# main.net
KiCad netlist of a schematic drawn in Altium Designer
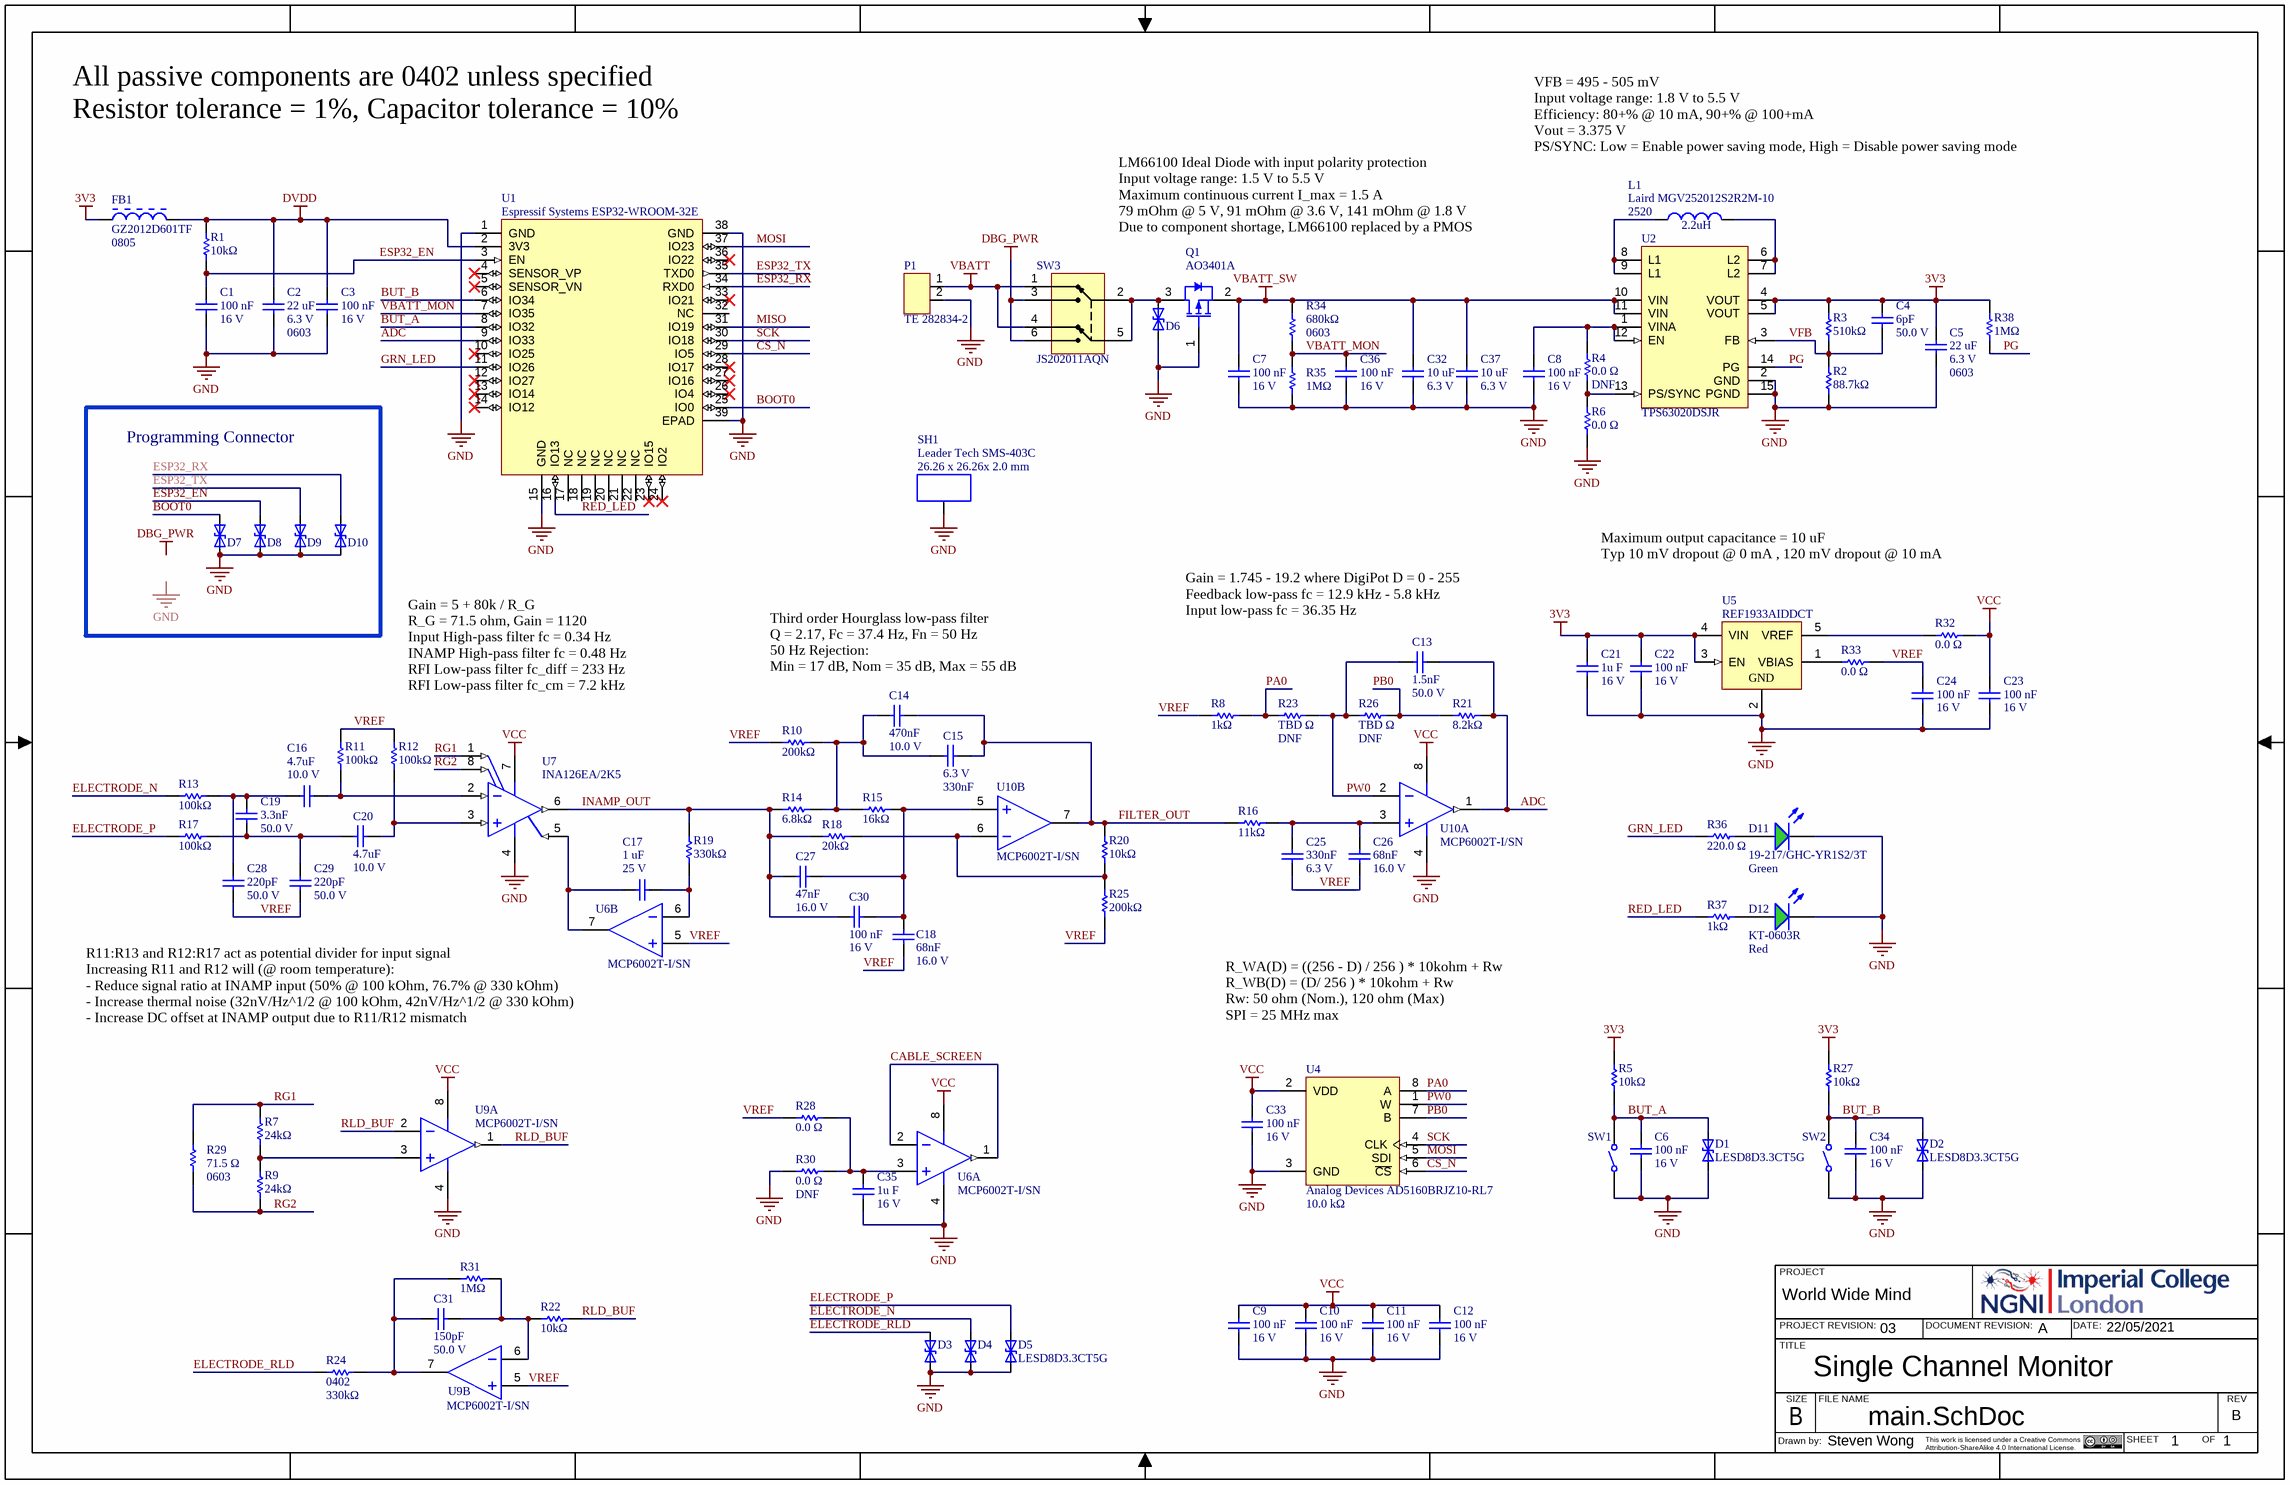
[diagram p0: main.SchDoc]

(export (version "E")
  (design (tool "Eeschema 10.0.6"))
  (components
    (comp (ref "C1")
      (value "100nF")
      (footprint "CAPC1005X56X25NL10T15")
      (description "Ceramic capacitor SMD-0402 100nF /16V X7R# K +-10%, Samsung, RoHS")
      (fields
        (field (name "CAPACITANCE") "100 nF")
        (field (name "VOLTAGE RATING") "16 V")
        (field (name "LCSC PART #") "C1525")
      )
      (libsource (lib "CommunityVault") (part "CMP-bf2276a55d9a60e5-19"))
    )
    (comp (ref "C2")
      (value "Murata GRM188R60G226MEA0L")
      (footprint "CAPC1608X90X35NL10T15")
      (description "Cap Ceramic 22uF 6.3V X5R 20% SMD 0603 85C Embossed T/R")
      (fields
        (field (name "CAPACITANCE") "22 uF")
        (field (name "VOLTAGE RATING (DC)") "6.3 V")
        (field (name "MANUFACTURER PART NUMBER") "GRM188R60G226MEA0L")
        (field (name "PACKAGE") "0603")
        (field (name "LCSC PART #") "C59461")
      )
      (libsource (lib "CommunityVault") (part "CMP-122043-3"))
    )
    (comp (ref "C3")
      (value "100nF")
      (footprint "CAPC1005X56X25NL10T15")
      (description "Ceramic capacitor SMD-0402 100nF /16V X7R# K +-10%, Samsung, RoHS")
      (fields
        (field (name "CAPACITANCE") "100 nF")
        (field (name "VOLTAGE RATING") "16 V")
        (field (name "LCSC PART #") "C1525")
      )
      (libsource (lib "CommunityVault") (part "CMP-bf2276a55d9a60e5-19"))
    )
    (comp (ref "C4")
      (value "AVX Interconnect / Elco 04025A6R0DAT2A")
      (footprint "CAPC1005X60X25NL10T15")
      (description "Multilayer Ceramic Capacitors MLCC - SMD/SMT 50volts 6pF C0G")
      (fields
        (field (name "CAPACITANCE") "6pF")
        (field (name "VOLTAGE RATING (DC)") "50.0 V")
        (field (name "MANUFACTURER PART NUMBER") "04025A6R0DAT2A")
        (field (name "LCSC PART #") "C30274")
      )
      (libsource (lib "CommunityVault") (part "CMP-173346-2"))
    )
    (comp (ref "C5")
      (value "Murata GRM188R60G226MEA0L")
      (footprint "CAPC1608X90X35NL10T15")
      (description "Cap Ceramic 22uF 6.3V X5R 20% SMD 0603 85C Embossed T/R")
      (fields
        (field (name "CAPACITANCE") "22 uF")
        (field (name "VOLTAGE RATING (DC)") "6.3 V")
        (field (name "MANUFACTURER PART NUMBER") "GRM188R60G226MEA0L")
        (field (name "PACKAGE") "0603")
        (field (name "LCSC PART #") "C59461")
      )
      (libsource (lib "CommunityVault") (part "CMP-122043-3"))
    )
    (comp (ref "C6")
      (value "100nF")
      (footprint "CAPC1005X56X25NL10T15")
      (description "Ceramic capacitor SMD-0402 100nF /16V X7R# K +-10%, Samsung, RoHS")
      (fields
        (field (name "CAPACITANCE") "100 nF")
        (field (name "VOLTAGE RATING") "16 V")
        (field (name "LCSC PART #") "C1525")
      )
      (libsource (lib "CommunityVault") (part "CMP-bf2276a55d9a60e5-19"))
    )
    (comp (ref "C7")
      (value "100nF")
      (footprint "CAPC1005X56X25NL10T15")
      (description "Ceramic capacitor SMD-0402 100nF /16V X7R# K +-10%, Samsung, RoHS")
      (fields
        (field (name "CAPACITANCE") "100 nF")
        (field (name "VOLTAGE RATING") "16 V")
        (field (name "LCSC PART #") "C1525")
      )
      (libsource (lib "CommunityVault") (part "CMP-bf2276a55d9a60e5-19"))
    )
    (comp (ref "C8")
      (value "100nF")
      (footprint "CAPC1005X56X25NL10T15")
      (description "Ceramic capacitor SMD-0402 100nF /16V X7R# K +-10%, Samsung, RoHS")
      (fields
        (field (name "CAPACITANCE") "100 nF")
        (field (name "VOLTAGE RATING") "16 V")
        (field (name "LCSC PART #") "C1525")
      )
      (libsource (lib "CommunityVault") (part "CMP-bf2276a55d9a60e5-19"))
    )
    (comp (ref "C9")
      (value "100nF")
      (footprint "CAPC1005X56X25NL10T15")
      (description "Ceramic capacitor SMD-0402 100nF /16V X7R# K +-10%, Samsung, RoHS")
      (fields
        (field (name "CAPACITANCE") "100 nF")
        (field (name "VOLTAGE RATING") "16 V")
        (field (name "LCSC PART #") "C1525")
      )
      (libsource (lib "CommunityVault") (part "CMP-bf2276a55d9a60e5-19"))
    )
    (comp (ref "C10")
      (value "100nF")
      (footprint "CAPC1005X56X25NL10T15")
      (description "Ceramic capacitor SMD-0402 100nF /16V X7R# K +-10%, Samsung, RoHS")
      (fields
        (field (name "CAPACITANCE") "100 nF")
        (field (name "VOLTAGE RATING") "16 V")
        (field (name "LCSC PART #") "C1525")
      )
      (libsource (lib "CommunityVault") (part "CMP-bf2276a55d9a60e5-19"))
    )
    (comp (ref "C11")
      (value "100nF")
      (footprint "CAPC1005X56X25NL10T15")
      (description "Ceramic capacitor SMD-0402 100nF /16V X7R# K +-10%, Samsung, RoHS")
      (fields
        (field (name "CAPACITANCE") "100 nF")
        (field (name "VOLTAGE RATING") "16 V")
        (field (name "LCSC PART #") "C1525")
      )
      (libsource (lib "CommunityVault") (part "CMP-bf2276a55d9a60e5-19"))
    )
    (comp (ref "C12")
      (value "100nF")
      (footprint "CAPC1005X56X25NL10T15")
      (description "Ceramic capacitor SMD-0402 100nF /16V X7R# K +-10%, Samsung, RoHS")
      (fields
        (field (name "CAPACITANCE") "100 nF")
        (field (name "VOLTAGE RATING") "16 V")
        (field (name "LCSC PART #") "C1525")
      )
      (libsource (lib "CommunityVault") (part "CMP-bf2276a55d9a60e5-19"))
    )
    (comp (ref "C13")
      (value "AVX Interconnect / Elco 04025C152KAT2A")
      (footprint "CAPC1005X56X25NL10T15")
      (description "Cap Ceramic 0.0015uF 50V X7R 10% SMD 0402 125C Paper T/R")
      (fields
        (field (name "MANUFACTURER PART NUMBER") "04025C152KAT2A")
        (field (name "CAPACITANCE") "1.5nF")
        (field (name "VOLTAGE RATING (DC)") "50.0 V")
        (field (name "LCSC PART #") "C23967")
      )
      (libsource (lib "CommunityVault") (part "CMP-126494-2"))
    )
    (comp (ref "C14")
      (value "AVX Interconnect / Elco 0402ZD474KAT2A")
      (footprint "CAPC1005X56X25NL10T15")
      (description "Multilayer Ceramic Capacitors MLCC - SMD/SMT 10volts 0.47uF 10% X5R")
      (fields
        (field (name "MANUFACTURER PART NUMBER") "0402ZD474KAT2A")
        (field (name "CAPACITANCE") "470nF")
        (field (name "VOLTAGE RATING (DC)") "10.0 V")
        (field (name "LCSC PART #") "C47339")
      )
      (libsource (lib "CommunityVault") (part "CMP-4106702-2"))
    )
    (comp (ref "C15")
      (value "CL05A334KQ5NNNC")
      (footprint "CAPC1005X55X25NL05T10")
      (description "CAP CER 0.33UF 10V 10% X5R 0402")
      (fields
        (field (name "VOLTAGE RATING (DC)") "6.3 V")
        (field (name "CAPACITANCE") "330nF")
        (field (name "LCSC PART #") "C307420")
      )
      (libsource (lib "CommunityVault") (part "CMP-119553-3"))
    )
    (comp (ref "C16")
      (value "CL05A475MP5NRNC")
      (footprint "CAPC1005X56X25NL10T15")
      (description "T&R / COMMERCIAL CHIP")
      (fields
        (field (name "CAPACITANCE") "4.7uF")
        (field (name "VOLTAGE RATING (DC)") "10.0 V")
        (field (name "LCSC PART #") "C23733")
      )
      (libsource (lib "CommunityVault") (part "CMP-19563753-2"))
    )
    (comp (ref "C17")
      (value "Samsung CL05A105KA5NQNC")
      (footprint "PCB-515da9ytrm2wahx6tw11-1")
      (description "Cap Ceramic 1uF 25V X5R 10% SMD 0402 85°C Cardboard T/R")
      (fields
        (field (name "VOLTAGE RATING (DC)") "25 V")
        (field (name "CAPACITANCE") "1 uF")
        (field (name "MANUFACTURER PART NUMBER") "CL05A105KA5NQNC")
        (field (name "LCSC PART #") "C52923")
      )
      (libsource (lib "CommunityVault") (part "CMP-8f214705328650e6-4"))
    )
    (comp (ref "C18")
      (value "Kemet C0402C683K4RACTU")
      (footprint "CAPC1005X55X30NL05T10")
      (description "CAP CER 0.068UF 16V 10% X7R 0402")
      (fields
        (field (name "CAPACITANCE") "68nF")
        (field (name "VOLTAGE RATING (DC)") "16.0 V")
        (field (name "MANUFACTURER PART NUMBER") "C0402C683K4RACTU")
        (field (name "LCSC PART #") "C12529")
      )
      (libsource (lib "CommunityVault") (part "CMP-124577-2"))
    )
    (comp (ref "C19")
      (value "AVX Interconnect / Elco 04025C332KAT2A")
      (footprint "CAPC1005X56X25NL10T15")
      (description "AVX   04025C332KAT2A   CAP, MLCC, X7R, 3.3NF, 50V, 0402")
      (fields
        (field (name "CAPACITANCE") "3.3nF")
        (field (name "VOLTAGE RATING (DC)") "50.0 V")
        (field (name "MANUFACTURER PART NUMBER") "04025C332KAT2A")
        (field (name "LCSC PART #") "C26404")
      )
      (libsource (lib "CommunityVault") (part "CMP-128367-2"))
    )
    (comp (ref "C20")
      (value "CL05A475MP5NRNC")
      (footprint "CAPC1005X56X25NL10T15")
      (description "T&R / COMMERCIAL CHIP")
      (fields
        (field (name "CAPACITANCE") "4.7uF")
        (field (name "VOLTAGE RATING (DC)") "10.0 V")
        (field (name "LCSC PART #") "C23733")
      )
      (libsource (lib "CommunityVault") (part "CMP-19563753-2"))
    )
    (comp (ref "C21")
      (value "Murata GRM155R61C105KA12D")
      (footprint "CAPC1005X55X25NL05T10")
      (description "Cap Ceramic 1uF 16V X5R 10% SMD 0402 85C Paper T/R")
      (fields
        (field (name "CAPACITANCE") "1u F")
        (field (name "VOLTAGE RATING (DC)") "16 V")
        (field (name "MANUFACTURER PART NUMBER") "GRM155R61C105KA12D")
        (field (name "LCSC PART #") "C52923")
      )
      (libsource (lib "CommunityVault") (part "CMP-7562325-2"))
    )
    (comp (ref "C22")
      (value "100nF")
      (footprint "CAPC1005X56X25NL10T15")
      (description "Ceramic capacitor SMD-0402 100nF /16V X7R# K +-10%, Samsung, RoHS")
      (fields
        (field (name "CAPACITANCE") "100 nF")
        (field (name "VOLTAGE RATING") "16 V")
        (field (name "LCSC PART #") "C1525")
      )
      (libsource (lib "CommunityVault") (part "CMP-bf2276a55d9a60e5-19"))
    )
    (comp (ref "C23")
      (value "100nF")
      (footprint "CAPC1005X56X25NL10T15")
      (description "Ceramic capacitor SMD-0402 100nF /16V X7R# K +-10%, Samsung, RoHS")
      (fields
        (field (name "CAPACITANCE") "100 nF")
        (field (name "VOLTAGE RATING") "16 V")
        (field (name "LCSC PART #") "C1525")
      )
      (libsource (lib "CommunityVault") (part "CMP-bf2276a55d9a60e5-19"))
    )
    (comp (ref "C24")
      (value "100nF")
      (footprint "CAPC1005X56X25NL10T15")
      (description "Ceramic capacitor SMD-0402 100nF /16V X7R# K +-10%, Samsung, RoHS")
      (fields
        (field (name "CAPACITANCE") "100 nF")
        (field (name "VOLTAGE RATING") "16 V")
        (field (name "LCSC PART #") "C1525")
      )
      (libsource (lib "CommunityVault") (part "CMP-bf2276a55d9a60e5-19"))
    )
    (comp (ref "C25")
      (value "CL05A334KQ5NNNC")
      (footprint "CAPC1005X55X25NL05T10")
      (description "CAP CER 0.33UF 10V 10% X5R 0402")
      (fields
        (field (name "VOLTAGE RATING (DC)") "6.3 V")
        (field (name "CAPACITANCE") "330nF")
        (field (name "LCSC PART #") "C307420")
      )
      (libsource (lib "CommunityVault") (part "CMP-119553-3"))
    )
    (comp (ref "C26")
      (value "Kemet C0402C683K4RACTU")
      (footprint "CAPC1005X55X30NL05T10")
      (description "CAP CER 0.068UF 16V 10% X7R 0402")
      (fields
        (field (name "CAPACITANCE") "68nF")
        (field (name "VOLTAGE RATING (DC)") "16.0 V")
        (field (name "MANUFACTURER PART NUMBER") "C0402C683K4RACTU")
        (field (name "LCSC PART #") "C12529")
      )
      (libsource (lib "CommunityVault") (part "CMP-124577-2"))
    )
    (comp (ref "C27")
      (value "AVX Interconnect / Elco 04023C473KAT2A")
      (footprint "CAPC1005X56X25NL10T15")
      (description "Multilayer Ceramic Capacitors MLCC - SMD/SMT 25volts 0.047uF 10% X7R 0402 SIZE")
      (fields
        (field (name "CAPACITANCE") "47nF")
        (field (name "VOLTAGE RATING (DC)") "16.0 V")
        (field (name "MANUFACTURER PART NUMBER") "04023C473KAT2A")
        (field (name "LCSC PART #") "C26403")
      )
      (libsource (lib "CommunityVault") (part "CMP-8988077-2"))
    )
    (comp (ref "C28")
      (value "Kemet C0402C221K5RACAUTO")
      (footprint "CAPC1005X55X30NL05T10")
      (description "CAPACITOR, 0402, X7R, 50V, 220PF")
      (fields
        (field (name "MANUFACTURER PART NUMBER") "C0402C221K5RACAUTO")
        (field (name "CAPACITANCE") "220pF")
        (field (name "VOLTAGE RATING (DC)") "50.0 V")
        (field (name "LCSC PART #") "C1530")
      )
      (libsource (lib "CommunityVault") (part "CMP-3913259-2"))
    )
    (comp (ref "C29")
      (value "Kemet C0402C221K5RACAUTO")
      (footprint "CAPC1005X55X30NL05T10")
      (description "CAPACITOR, 0402, X7R, 50V, 220PF")
      (fields
        (field (name "MANUFACTURER PART NUMBER") "C0402C221K5RACAUTO")
        (field (name "CAPACITANCE") "220pF")
        (field (name "VOLTAGE RATING (DC)") "50.0 V")
        (field (name "LCSC PART #") "C1530")
      )
      (libsource (lib "CommunityVault") (part "CMP-3913259-2"))
    )
    (comp (ref "C30")
      (value "100nF")
      (footprint "CAPC1005X56X25NL10T15")
      (description "Ceramic capacitor SMD-0402 100nF /16V X7R# K +-10%, Samsung, RoHS")
      (fields
        (field (name "CAPACITANCE") "100 nF")
        (field (name "VOLTAGE RATING") "16 V")
        (field (name "LCSC PART #") "C1525")
      )
      (libsource (lib "CommunityVault") (part "CMP-bf2276a55d9a60e5-19"))
    )
    (comp (ref "C31")
      (value "AVX Interconnect / Elco 04025A151JAT2A")
      (footprint "CAPC1005X56X25NL10T15")
      (description "AVX   04025A151JAT2A   CAP, MLCC, C0G/NP0, 150PF, 50V, 0402")
      (fields
        (field (name "CAPACITANCE") "150pF")
        (field (name "VOLTAGE RATING (DC)") "50.0 V")
        (field (name "MANUFACTURER PART NUMBER") "04025A151JAT2A")
        (field (name "LCSC PART #") "C1527")
      )
      (libsource (lib "CommunityVault") (part "CMP-128358-2"))
    )
    (comp (ref "C32")
      (value "Samsung CL05A106MQ5NUNC")
      (footprint "PCB-a41llqp6xpt8gy62f2hk-1")
      (description "Cap Ceramic 10uF 6.3V X5R 20% SMD 0402 85°C Paper T/R")
      (fields
        (field (name "MANUFACTURER PART NUMBER") "CL05A106MQ5NUNC")
        (field (name "VOLTAGE RATING (DC)") "6.3 V")
        (field (name "CAPACITANCE") "10 uF")
        (field (name "LCSC PART #") "C15525")
      )
      (libsource (lib "CommunityVault") (part "CMP-fd5e350784e62299-2"))
    )
    (comp (ref "C33")
      (value "100nF")
      (footprint "CAPC1005X56X25NL10T15")
      (description "Ceramic capacitor SMD-0402 100nF /16V X7R# K +-10%, Samsung, RoHS")
      (fields
        (field (name "CAPACITANCE") "100 nF")
        (field (name "VOLTAGE RATING") "16 V")
        (field (name "LCSC PART #") "C1525")
      )
      (libsource (lib "CommunityVault") (part "CMP-bf2276a55d9a60e5-19"))
    )
    (comp (ref "C34")
      (value "100nF")
      (footprint "CAPC1005X56X25NL10T15")
      (description "Ceramic capacitor SMD-0402 100nF /16V X7R# K +-10%, Samsung, RoHS")
      (fields
        (field (name "CAPACITANCE") "100 nF")
        (field (name "VOLTAGE RATING") "16 V")
        (field (name "LCSC PART #") "C1525")
      )
      (libsource (lib "CommunityVault") (part "CMP-bf2276a55d9a60e5-19"))
    )
    (comp (ref "C35")
      (value "Murata GRM155R61C105KA12D")
      (footprint "CAPC1005X55X25NL05T10")
      (description "Cap Ceramic 1uF 16V X5R 10% SMD 0402 85C Paper T/R")
      (fields
        (field (name "CAPACITANCE") "1u F")
        (field (name "VOLTAGE RATING (DC)") "16 V")
        (field (name "MANUFACTURER PART NUMBER") "GRM155R61C105KA12D")
        (field (name "LCSC PART #") "C52923")
      )
      (libsource (lib "CommunityVault") (part "CMP-7562325-2"))
    )
    (comp (ref "C36")
      (value "100nF")
      (footprint "CAPC1005X56X25NL10T15")
      (description "Ceramic capacitor SMD-0402 100nF /16V X7R# K +-10%, Samsung, RoHS")
      (fields
        (field (name "CAPACITANCE") "100 nF")
        (field (name "VOLTAGE RATING") "16 V")
        (field (name "LCSC PART #") "C1525")
      )
      (libsource (lib "CommunityVault") (part "CMP-bf2276a55d9a60e5-19"))
    )
    (comp (ref "C37")
      (value "Samsung CL05A106MQ5NUNC")
      (footprint "PCB-a41llqp6xpt8gy62f2hk-1")
      (description "Cap Ceramic 10uF 6.3V X5R 20% SMD 0402 85°C Paper T/R")
      (fields
        (field (name "MANUFACTURER PART NUMBER") "CL05A106MQ5NUNC")
        (field (name "VOLTAGE RATING (DC)") "6.3 V")
        (field (name "CAPACITANCE") "10 uF")
        (field (name "LCSC PART #") "C15525")
      )
      (libsource (lib "CommunityVault") (part "CMP-fd5e350784e62299-2"))
    )
    (comp (ref "D1")
      (value "LESD8D3.3CT5G")
      (footprint "DFN64P100X50-2N")
      (description "Bidirectional 3.3V (Max) 5V 14.1V 11.2A(8/20us) SOD-882 Diodes - ESD RoHS")
      (fields (field (name "MANUFACTURER") "LRC") (field (name "LCSC PART #") "C172410"))
      (libsource (lib "FavoritesLibrary") (part "SYM-zjatvudan2pmebzuzrjd-1"))
    )
    (comp (ref "D2")
      (value "LESD8D3.3CT5G")
      (footprint "DFN64P100X50-2N")
      (description "Bidirectional 3.3V (Max) 5V 14.1V 11.2A(8/20us) SOD-882 Diodes - ESD RoHS")
      (fields (field (name "MANUFACTURER") "LRC") (field (name "LCSC PART #") "C172410"))
      (libsource (lib "FavoritesLibrary") (part "SYM-zjatvudan2pmebzuzrjd-1"))
    )
    (comp (ref "D3")
      (value "LESD8D3.3CT5G")
      (footprint "DFN64P100X50-2N")
      (description "Bidirectional 3.3V (Max) 5V 14.1V 11.2A(8/20us) SOD-882 Diodes - ESD RoHS")
      (fields (field (name "MANUFACTURER") "LRC") (field (name "LCSC PART #") "C172410"))
      (libsource (lib "FavoritesLibrary") (part "SYM-zjatvudan2pmebzuzrjd-1"))
    )
    (comp (ref "D4")
      (value "LESD8D3.3CT5G")
      (footprint "DFN64P100X50-2N")
      (description "Bidirectional 3.3V (Max) 5V 14.1V 11.2A(8/20us) SOD-882 Diodes - ESD RoHS")
      (fields (field (name "MANUFACTURER") "LRC") (field (name "LCSC PART #") "C172410"))
      (libsource (lib "FavoritesLibrary") (part "SYM-zjatvudan2pmebzuzrjd-1"))
    )
    (comp (ref "D5")
      (value "LESD8D3.3CT5G")
      (footprint "DFN64P100X50-2N")
      (description "Bidirectional 3.3V (Max) 5V 14.1V 11.2A(8/20us) SOD-882 Diodes - ESD RoHS")
      (fields (field (name "MANUFACTURER") "LRC") (field (name "LCSC PART #") "C172410"))
      (libsource (lib "FavoritesLibrary") (part "SYM-zjatvudan2pmebzuzrjd-1"))
    )
    (comp (ref "D6")
      (value "LESD8D3.3CT5G")
      (footprint "DFN64P100X50-2N")
      (description "Bidirectional 3.3V (Max) 5V 14.1V 11.2A(8/20us) SOD-882 Diodes - ESD RoHS")
      (fields (field (name "MANUFACTURER") "LRC") (field (name "LCSC PART #") "C172410"))
      (libsource (lib "FavoritesLibrary") (part "SYM-zjatvudan2pmebzuzrjd-1"))
    )
    (comp (ref "D7")
      (value "LESD8D3.3CT5G")
      (footprint "DFN64P100X50-2N")
      (description "Bidirectional 3.3V (Max) 5V 14.1V 11.2A(8/20us) SOD-882 Diodes - ESD RoHS")
      (fields (field (name "MANUFACTURER") "LRC") (field (name "LCSC PART #") "C172410"))
      (libsource (lib "FavoritesLibrary") (part "SYM-zjatvudan2pmebzuzrjd-1"))
    )
    (comp (ref "D8")
      (value "LESD8D3.3CT5G")
      (footprint "DFN64P100X50-2N")
      (description "Bidirectional 3.3V (Max) 5V 14.1V 11.2A(8/20us) SOD-882 Diodes - ESD RoHS")
      (fields (field (name "MANUFACTURER") "LRC") (field (name "LCSC PART #") "C172410"))
      (libsource (lib "FavoritesLibrary") (part "SYM-zjatvudan2pmebzuzrjd-1"))
    )
    (comp (ref "D9")
      (value "LESD8D3.3CT5G")
      (footprint "DFN64P100X50-2N")
      (description "Bidirectional 3.3V (Max) 5V 14.1V 11.2A(8/20us) SOD-882 Diodes - ESD RoHS")
      (fields (field (name "MANUFACTURER") "LRC") (field (name "LCSC PART #") "C172410"))
      (libsource (lib "FavoritesLibrary") (part "SYM-zjatvudan2pmebzuzrjd-1"))
    )
    (comp (ref "D10")
      (value "LESD8D3.3CT5G")
      (footprint "DFN64P100X50-2N")
      (description "Bidirectional 3.3V (Max) 5V 14.1V 11.2A(8/20us) SOD-882 Diodes - ESD RoHS")
      (fields (field (name "MANUFACTURER") "LRC") (field (name "LCSC PART #") "C172410"))
      (libsource (lib "FavoritesLibrary") (part "SYM-zjatvudan2pmebzuzrjd-1"))
    )
    (comp (ref "D11")
      (value "19-217/GHC-YR1S2/3T")
      (footprint "PCB-qrh50x9m6cshxb6d9t7t-1")
      (description "LED SMD Top View Uni-Color Brilliant Green 518nm 0603 Pkg ø7T/R 3k\"")
      (fields (field (name "LCSC PART #") "C72043") (field (name "COLOUR") "Green"))
      (libsource (lib "CommunityVault") (part "CMP-7093b92408b7af54-1"))
    )
    (comp (ref "D12")
      (value "KT-0603R")
      (footprint "PCB-qrh50x9m6cshxb6d9t7t-1")
      (description "LED SMD Top View Uni-Color Brilliant Green 518nm 0603 Pkg ø7T/R 3k\"")
      (fields (field (name "LCSC PART #") "C2286") (field (name "COLOUR") "Red"))
      (libsource (lib "CommunityVault") (part "CMP-7093b92408b7af54-1"))
    )
    (comp (ref "FB1")
      (value "GZ2012D601TF")
      (footprint "MURA-BLM21-H1-CHIP-2_V")
      (fields
        (field (name "CASE/PACKAGE") "0805")
        (field (name "MANUFACTURER PART NUMBER") "BLM21BB331SN1D")
        (field (name "LCSC PART #") "C1017")
      )
      (libsource (lib "CommunityVault") (part "CMP-887293-3"))
    )
    (comp (ref "L1")
      (value "Laird MGV252012S2R2M-10")
      (footprint "INDM2520X12N")
      (description "MGV252012 - High Current Molded SMT Power Inductor")
      (fields
        (field (name "MANUFACTURER PART NUMBER") "MGV252012S2R2M-10")
        (field (name "LCSC PART #") "C375952")
        (field (name "INDUCTANCE") "2.2uH")
        (field (name "PACKAGE") "2520")
      )
      (libsource (lib "CommunityVault") (part "CMP-6756ab2d39beb891-1"))
    )
    (comp (ref "P1")
      (value "TE 282834-2")
      (footprint "PCB-6xrngco598u3mra2uzi2-1")
      (description "Wire-To-Board Terminal Block, 2, 150 V, 10 A, 30 Awg, 16 Awg, 1.4 Mm")
      (libsource (lib "CommunityVault") (part "SYM-4e52859dc8429195-14"))
    )
    (comp (ref "Q1")
      (value "AO3401A")
      (footprint "PCB-kx100zt0qwbp6gbfpfbn-1")
      (description "MOSFET P-CH 30V 4A SOT23")
      (fields (field (name "MANUFACTURER") "Alpha & Omega Semicon") (field (name "LCSC PART #") "C15127"))
      (libsource (lib "CommunityVault") (part "CMP-832298-9"))
    )
    (comp (ref "R1")
      (value "Yageo / Phycomp RC0402FR-1310KL")
      (footprint "RESC1005X40X25NL05T10")
      (description "Thick Film Resistors - SMD 10K OHM 1%")
      (fields
        (field (name "RESISTANCE") "10kΩ")
        (field (name "MANUFACTURER PART NUMBER") "RC0402FR-1310KL")
        (field (name "LCSC PART #") "C25744")
      )
      (libsource (lib "CommunityVault") (part "CMP-3661304-2"))
    )
    (comp (ref "R2")
      (value "Panasonic ERJ-2RKF8872X")
      (footprint "RESC1005X40X25NL05T05")
      (description "Thick Film Resistors - SMD 0402 88.7Kohms 1% Tol")
      (fields
        (field (name "RESISTANCE") "88.7kΩ")
        (field (name "MANUFACTURER PART NUMBER") "ERJ-2RKF8872X")
        (field (name "LCSC PART #") "C25922")
      )
      (libsource (lib "CommunityVault") (part "CMP-3682312-2"))
    )
    (comp (ref "R3")
      (value "Vishay Dale CRCW0402510KFKED")
      (footprint "RESC1005X40X25NL05T05")
      (description "RES SMD 510K OHM 1% 1/16W 0402")
      (fields
        (field (name "RESISTANCE") "510kΩ")
        (field (name "MANUFACTURER PART NUMBER") "CRCW0402510KFKED")
        (field (name "LCSC PART #") "C11616")
      )
      (libsource (lib "CommunityVault") (part "CMP-3945506-8"))
    )
    (comp (ref "R4")
      (value "Yageo AC0402JR-070RL")
      (footprint "RESC1005X37X25NL05T10")
      (description "RES SMD 0.0 OHM JUMPER 1/16W")
      (fields
        (field (name "MANUFACTURER PART NUMBER") "AC0402JR-070RL")
        (field (name "RESISTANCE") "0.0 Ω")
        (field (name "LCSC PART #") "C17168")
        (field (name "FIT") "DNF")
      )
      (libsource (lib "CommunityVault") (part "CMP-1900348-2"))
    )
    (comp (ref "R5")
      (value "Yageo / Phycomp RC0402FR-1310KL")
      (footprint "RESC1005X40X25NL05T10")
      (description "Thick Film Resistors - SMD 10K OHM 1%")
      (fields
        (field (name "RESISTANCE") "10kΩ")
        (field (name "MANUFACTURER PART NUMBER") "RC0402FR-1310KL")
        (field (name "LCSC PART #") "C25744")
      )
      (libsource (lib "CommunityVault") (part "CMP-3661304-2"))
    )
    (comp (ref "R6")
      (value "Yageo AC0402JR-070RL")
      (footprint "RESC1005X37X25NL05T10")
      (description "RES SMD 0.0 OHM JUMPER 1/16W")
      (fields
        (field (name "MANUFACTURER PART NUMBER") "AC0402JR-070RL")
        (field (name "RESISTANCE") "0.0 Ω")
        (field (name "LCSC PART #") "C17168")
      )
      (libsource (lib "CommunityVault") (part "CMP-1900348-2"))
    )
    (comp (ref "R7")
      (value "Yageo / Phycomp RC0402FR-0724KL")
      (footprint "RESC1005X40X25NL05T10")
      (description "RESISTOR, 0402 0.063W 1% 24K")
      (fields
        (field (name "MANUFACTURER PART NUMBER") "RC0402FR-0724KL")
        (field (name "RESISTANCE") "24kΩ")
        (field (name "LCSC PART #") "C25769")
      )
      (libsource (lib "CommunityVault") (part "CMP-1900184-2"))
    )
    (comp (ref "R8")
      (value "KOA Speer RK73H1ETTP1001F")
      (footprint "RESC1005X40X25NL10T10")
      (description "Res Thick Film 0402 1K Ohm 1% 0.063W(1/16W) ±100ppm/C Molded SMD Automotive Punched Paper T/R")
      (fields
        (field (name "RESISTANCE") "1kΩ")
        (field (name "MANUFACTURER PART NUMBER") "RK73H1ETTP1001F")
        (field (name "LCSC PART #") "C11702")
      )
      (libsource (lib "CommunityVault") (part "CMP-2823544-2"))
    )
    (comp (ref "R9")
      (value "Yageo / Phycomp RC0402FR-0724KL")
      (footprint "RESC1005X40X25NL05T10")
      (description "RESISTOR, 0402 0.063W 1% 24K")
      (fields
        (field (name "MANUFACTURER PART NUMBER") "RC0402FR-0724KL")
        (field (name "RESISTANCE") "24kΩ")
        (field (name "LCSC PART #") "C25769")
      )
      (libsource (lib "CommunityVault") (part "CMP-1900184-2"))
    )
    (comp (ref "R10")
      (value "KOA Speer RK73H1ETTP2003F")
      (footprint "RESC1005X40X25NL10T10")
      (description "Res Thick Film 0402 200K Ohm 1% 0.063W(1/16W) ±100ppm/C Molded SMD Automotive Punched Paper T/R")
      (fields
        (field (name "MANUFACTURER PART NUMBER") "RK73H1ETTP2003F")
        (field (name "RESISTANCE") "200kΩ")
        (field (name "LCSC PART #") "C25764")
      )
      (libsource (lib "CommunityVault") (part "CMP-2823564-2"))
    )
    (comp (ref "R11")
      (value "Yageo RC0402FR-13100KL")
      (footprint "RESC1005X40X25NL05T10")
      (description "YAGEO   RC0402FR-13100KL   THICK FILM RESISTOR, 100KOHM, 62.5mW 1%")
      (fields
        (field (name "MANUFACTURER PART NUMBER") "RC0402FR-13100KL")
        (field (name "RESISTANCE") "100kΩ")
        (field (name "LCSC PART #") "C25741")
      )
      (libsource (lib "CommunityVault") (part "CMP-3759242-3"))
    )
    (comp (ref "R12")
      (value "Yageo RC0402FR-13100KL")
      (footprint "RESC1005X40X25NL05T10")
      (description "YAGEO   RC0402FR-13100KL   THICK FILM RESISTOR, 100KOHM, 62.5mW 1%")
      (fields
        (field (name "MANUFACTURER PART NUMBER") "RC0402FR-13100KL")
        (field (name "RESISTANCE") "100kΩ")
        (field (name "LCSC PART #") "C25741")
      )
      (libsource (lib "CommunityVault") (part "CMP-3759242-3"))
    )
    (comp (ref "R13")
      (value "Yageo RC0402FR-13100KL")
      (footprint "RESC1005X40X25NL05T10")
      (description "YAGEO   RC0402FR-13100KL   THICK FILM RESISTOR, 100KOHM, 62.5mW 1%")
      (fields
        (field (name "MANUFACTURER PART NUMBER") "RC0402FR-13100KL")
        (field (name "RESISTANCE") "100kΩ")
        (field (name "LCSC PART #") "C25741")
      )
      (libsource (lib "CommunityVault") (part "CMP-3759242-3"))
    )
    (comp (ref "R14")
      (value "Vishay Dale CRCW04026K80FKED")
      (footprint "RESC1005X40X25NL05T05")
      (description "RES SMD 6.8K OHM 1% 1/16W 0402")
      (fields
        (field (name "RESISTANCE") "6.8kΩ")
        (field (name "MANUFACTURER PART NUMBER") "CRCW04026K80FKED")
        (field (name "LCSC PART #") "C25917")
      )
      (libsource (lib "CommunityVault") (part "CMP-1856508-2"))
    )
    (comp (ref "R15")
      (value "Yageo / Phycomp RC0402FR-0716KL")
      (footprint "RESC1005X40X25NL05T10")
      (description "YAGEO (PHYCOMP)   RC0402FR-0716KL   RESISTOR, 0402 0.063W 1% 16K")
      (fields
        (field (name "MANUFACTURER PART NUMBER") "RC0402FR-0716KL")
        (field (name "RESISTANCE") "16kΩ")
        (field (name "LCSC PART #") "C25759")
      )
      (libsource (lib "CommunityVault") (part "CMP-1853199-2"))
    )
    (comp (ref "R16")
      (value "Yageo / Phycomp RC0402FR-0711KL")
      (footprint "RESC1005X40X25NL05T10")
      (description "RES SMD 11K OHM 1% 1/16W 0402")
      (fields
        (field (name "RESISTANCE") "11kΩ")
        (field (name "MANUFACTURER PART NUMBER") "RC0402FR-0711KL")
        (field (name "LCSC PART #") "C25749")
      )
      (libsource (lib "CommunityVault") (part "CMP-1853185-2"))
    )
    (comp (ref "R17")
      (value "Yageo RC0402FR-13100KL")
      (footprint "RESC1005X40X25NL05T10")
      (description "YAGEO   RC0402FR-13100KL   THICK FILM RESISTOR, 100KOHM, 62.5mW 1%")
      (fields
        (field (name "MANUFACTURER PART NUMBER") "RC0402FR-13100KL")
        (field (name "RESISTANCE") "100kΩ")
        (field (name "LCSC PART #") "C25741")
      )
      (libsource (lib "CommunityVault") (part "CMP-3759242-3"))
    )
    (comp (ref "R18")
      (value "Panasonic ERJ-2RKF2002X")
      (footprint "RESC1005X40X25NL05T05")
      (description "Thick Film Resistors - SMD 0402 20Kohms 1% Tol")
      (fields
        (field (name "RESISTANCE") "20kΩ")
        (field (name "MANUFACTURER PART NUMBER") "ERJ-2RKF2002X")
        (field (name "LCSC PART #") "C25765")
      )
      (libsource (lib "CommunityVault") (part "CMP-3656287-2"))
    )
    (comp (ref "R19")
      (value "Vishay Dale CRCW0402330KFKED")
      (footprint "RESC1005X40X25NL05T05")
      (description "RES SMD 330K OHM 1% 1/16W 0402")
      (fields
        (field (name "RESISTANCE") "330kΩ")
        (field (name "MANUFACTURER PART NUMBER") "CRCW0402330KFKED")
        (field (name "LCSC PART #") "C25778")
      )
      (libsource (lib "CommunityVault") (part "CMP-1856416-2"))
    )
    (comp (ref "R20")
      (value "Yageo / Phycomp RC0402FR-1310KL")
      (footprint "RESC1005X40X25NL05T10")
      (description "Thick Film Resistors - SMD 10K OHM 1%")
      (fields
        (field (name "RESISTANCE") "10kΩ")
        (field (name "MANUFACTURER PART NUMBER") "RC0402FR-1310KL")
        (field (name "LCSC PART #") "C25744")
      )
      (libsource (lib "CommunityVault") (part "CMP-3661304-2"))
    )
    (comp (ref "R21")
      (value "Yageo AC0402FR-078K2L")
      (footprint "RESC1005X37X25NL05T10")
      (description "0402 8.2k ohms 1% automotive grade chip resistor")
      (fields
        (field (name "MANUFACTURER PART NUMBER") "AC0402FR-078K2L")
        (field (name "RESISTANCE") "8.2kΩ")
        (field (name "LCSC PART #") "C25924")
      )
      (libsource (lib "CommunityVault") (part "CMP-9399996-2"))
    )
    (comp (ref "R22")
      (value "Yageo / Phycomp RC0402FR-1310KL")
      (footprint "RESC1005X40X25NL05T10")
      (description "Thick Film Resistors - SMD 10K OHM 1%")
      (fields
        (field (name "RESISTANCE") "10kΩ")
        (field (name "MANUFACTURER PART NUMBER") "RC0402FR-1310KL")
        (field (name "LCSC PART #") "C25744")
      )
      (libsource (lib "CommunityVault") (part "CMP-3661304-2"))
    )
    (comp (ref "R23")
      (value "Yageo / Phycomp RC0402FR-1310KL")
      (footprint "RESC1005X40X25NL05T10")
      (description "Thick Film Resistors - SMD 10K OHM 1%")
      (fields
        (field (name "RESISTANCE") "TBD Ω")
        (field (name "MANUFACTURER PART NUMBER") "RC0402FR-1310KL")
        (field (name "FIT") "DNF")
        (field (name "LCSC PART #") "C25744")
      )
      (libsource (lib "CommunityVault") (part "CMP-3661304-2"))
    )
    (comp (ref "R24")
      (value "Vishay Dale CRCW0402330KFKED")
      (footprint "RESC1005X40X25NL05T05")
      (description "RES SMD 330K OHM 1% 1/16W 0402")
      (fields
        (field (name "CASE/PACKAGE") "0402")
        (field (name "RESISTANCE") "330kΩ")
        (field (name "MANUFACTURER PART NUMBER") "CRCW0402330KFKED")
        (field (name "LCSC PART #") "C25778")
      )
      (libsource (lib "CommunityVault") (part "CMP-1856416-2"))
    )
    (comp (ref "R25")
      (value "KOA Speer RK73H1ETTP2003F")
      (footprint "RESC1005X40X25NL10T10")
      (description "Res Thick Film 0402 200K Ohm 1% 0.063W(1/16W) ±100ppm/C Molded SMD Automotive Punched Paper T/R")
      (fields
        (field (name "MANUFACTURER PART NUMBER") "RK73H1ETTP2003F")
        (field (name "RESISTANCE") "200kΩ")
        (field (name "LCSC PART #") "C25764")
      )
      (libsource (lib "CommunityVault") (part "CMP-2823564-2"))
    )
    (comp (ref "R26")
      (value "Yageo / Phycomp RC0402FR-1310KL")
      (footprint "RESC1005X40X25NL05T10")
      (description "Thick Film Resistors - SMD 10K OHM 1%")
      (fields
        (field (name "RESISTANCE") "TBD Ω")
        (field (name "MANUFACTURER PART NUMBER") "RC0402FR-1310KL")
        (field (name "FIT") "DNF")
        (field (name "LCSC PART #") "C25744")
      )
      (libsource (lib "CommunityVault") (part "CMP-3661304-2"))
    )
    (comp (ref "R27")
      (value "Yageo / Phycomp RC0402FR-1310KL")
      (footprint "RESC1005X40X25NL05T10")
      (description "Thick Film Resistors - SMD 10K OHM 1%")
      (fields
        (field (name "RESISTANCE") "10kΩ")
        (field (name "MANUFACTURER PART NUMBER") "RC0402FR-1310KL")
        (field (name "LCSC PART #") "C25744")
      )
      (libsource (lib "CommunityVault") (part "CMP-3661304-2"))
    )
    (comp (ref "R28")
      (value "Yageo AC0402JR-070RL")
      (footprint "RESC1005X37X25NL05T10")
      (description "RES SMD 0.0 OHM JUMPER 1/16W")
      (fields
        (field (name "MANUFACTURER PART NUMBER") "AC0402JR-070RL")
        (field (name "RESISTANCE") "0.0 Ω")
        (field (name "LCSC PART #") "C17168")
      )
      (libsource (lib "CommunityVault") (part "CMP-1900348-2"))
    )
    (comp (ref "R29")
      (value "Panasonic ERJ-3EKF71R5V")
      (footprint "RESC1608X55X30NL15T15")
      (description "Thick Film Resistors - SMD 0603 71.5ohms 1% Tol")
      (fields
        (field (name "CASE/PACKAGE") "0603")
        (field (name "RESISTANCE") "71.5 Ω")
        (field (name "MANUFACTURER PART NUMBER") "ERJ-3EKF71R5V")
        (field (name "LCSC PART #") "C23104")
      )
      (libsource (lib "CommunityVault") (part "CMP-3679617-2"))
    )
    (comp (ref "R30")
      (value "Yageo AC0402JR-070RL")
      (footprint "RESC1005X37X25NL05T10")
      (description "RES SMD 0.0 OHM JUMPER 1/16W")
      (fields
        (field (name "MANUFACTURER PART NUMBER") "AC0402JR-070RL")
        (field (name "RESISTANCE") "0.0 Ω")
        (field (name "LCSC PART #") "C17168")
        (field (name "FIT") "DNF")
      )
      (libsource (lib "CommunityVault") (part "CMP-1900348-2"))
    )
    (comp (ref "R31")
      (value "Yageo AC0402FR-071ML")
      (footprint "RESC1005X37X25NL05T10")
      (description "Thick Film Resistors 1/16W 1M ohm 1%")
      (fields
        (field (name "MANUFACTURER PART NUMBER") "AC0402FR-071ML")
        (field (name "RESISTANCE") "1MΩ")
        (field (name "LCSC PART #") "C26083")
      )
      (libsource (lib "CommunityVault") (part "CMP-7833283-2"))
    )
    (comp (ref "R32")
      (value "Yageo AC0402JR-070RL")
      (footprint "RESC1005X37X25NL05T10")
      (description "RES SMD 0.0 OHM JUMPER 1/16W")
      (fields
        (field (name "MANUFACTURER PART NUMBER") "AC0402JR-070RL")
        (field (name "RESISTANCE") "0.0 Ω")
        (field (name "LCSC PART #") "C17168")
      )
      (libsource (lib "CommunityVault") (part "CMP-1900348-2"))
    )
    (comp (ref "R33")
      (value "Yageo AC0402JR-070RL")
      (footprint "RESC1005X37X25NL05T10")
      (description "RES SMD 0.0 OHM JUMPER 1/16W")
      (fields
        (field (name "MANUFACTURER PART NUMBER") "AC0402JR-070RL")
        (field (name "RESISTANCE") "0.0 Ω")
        (field (name "LCSC PART #") "C17168")
      )
      (libsource (lib "CommunityVault") (part "CMP-1900348-2"))
    )
    (comp (ref "R34")
      (value "Vishay Dale CRCW0603680KFKEA")
      (footprint "RESC1609X50X30NL10T20")
      (description "RES SMD 680K OHM 1% 1/10W 0603")
      (fields
        (field (name "CASE/PACKAGE") "0603")
        (field (name "RESISTANCE") "680kΩ")
        (field (name "MANUFACTURER PART NUMBER") "CRCW0603680KFKEA")
        (field (name "LCSC PART #") "C25822")
      )
      (libsource (lib "CommunityVault") (part "CMP-1873487-2"))
    )
    (comp (ref "R35")
      (value "Yageo AC0402FR-071ML")
      (footprint "RESC1005X37X25NL05T10")
      (description "Thick Film Resistors 1/16W 1M ohm 1%")
      (fields
        (field (name "MANUFACTURER PART NUMBER") "AC0402FR-071ML")
        (field (name "RESISTANCE") "1MΩ")
        (field (name "LCSC PART #") "C26083")
      )
      (libsource (lib "CommunityVault") (part "CMP-7833283-2"))
    )
    (comp (ref "R36")
      (value "Vishay Dale CRCW0402220RFKED")
      (footprint "RESC1005X40X25NL05T05")
      (description "RES SMD 220 OHM 1% 1/16W 0402")
      (fields
        (field (name "RESISTANCE") "220.0 Ω")
        (field (name "MANUFACTURER PART NUMBER") "CRCW0402220RFKED")
        (field (name "LCSC PART #") "C25091")
      )
      (libsource (lib "CommunityVault") (part "CMP-1867363-2"))
    )
    (comp (ref "R37")
      (value "Panasonic ERJ-U02F1001X")
      (footprint "RESC1005X40X25NL05T10")
      (description "Thick Film Resistors - SMD 0402 1% 1.0Kohm Anti-Sulfur")
      (fields
        (field (name "MANUFACTURER PART NUMBER") "ERJ-U02F1001X")
        (field (name "RESISTANCE") "1kΩ")
        (field (name "LCSC PART #") "C11702")
      )
      (libsource (lib "CommunityVault") (part "CMP-9105019-2"))
    )
    (comp (ref "R38")
      (value "Yageo AC0402FR-071ML")
      (footprint "RESC1005X37X25NL05T10")
      (description "Thick Film Resistors 1/16W 1M ohm 1%")
      (fields
        (field (name "MANUFACTURER PART NUMBER") "AC0402FR-071ML")
        (field (name "RESISTANCE") "1MΩ")
        (field (name "LCSC PART #") "C26083")
      )
      (libsource (lib "CommunityVault") (part "CMP-7833283-2"))
    )
    (comp (ref "SH1")
      (value "Leader Tech SMS-403C")
      (footprint "PCB-mz3zksww60jqn1djdwiu-1")
      (fields
        (field (name "MANUFACTURER PART NUMBER") "SMS-403C")
        (field (name "SIZE") "26.26 x 26.26x 2.0 mm")
      )
      (libsource (lib "CommunityVault") (part "CMP-da641787f57f05a3-1"))
    )
    (comp (ref "SW1")
      (value "TS-1185-C-A-A-A")
      (footprint "PCB-qarcnbrnejma51b9hfzm-1")
      (description "SPST 50mA @ 12VDC Vertical Round Button 260gf SMD Tactile Switches RoHS")
      (fields (field (name "LCSC PART #") "C561518") (field (name "MANUFACTURER") "XKB Connectivity"))
      (libsource (lib "FavoritesLibrary") (part "SYM-hgui3ccx9uakpoe7vbsx-1"))
    )
    (comp (ref "SW2")
      (value "TS-1185-C-A-A-A")
      (footprint "PCB-qarcnbrnejma51b9hfzm-1")
      (description "SPST 50mA @ 12VDC Vertical Round Button 260gf SMD Tactile Switches RoHS")
      (fields (field (name "LCSC PART #") "C561518") (field (name "MANUFACTURER") "XKB Connectivity"))
      (libsource (lib "FavoritesLibrary") (part "SYM-hgui3ccx9uakpoe7vbsx-1"))
    )
    (comp (ref "SW3")
      (value "JS202011AQN")
      (footprint "PCB-wbq3apgbd2bliremr4t3-1")
      (description "Switch Slide DPDT Side Slide 0.3A 30VDC PC Pins Thru-Hole Bulk")
      (fields (field (name "LCSC PART #") "C221662"))
      (libsource (lib "CommunityVault") (part "CMP-c7970ef1edec1850-5"))
    )
    (comp (ref "U1")
      (value "Espressif Systems ESP32-WROOM-32E")
      (footprint "ESP32-WROOM-32E")
      (description "Rx Txrx Mod Wifi Trace Ant SMD")
      (fields
        (field (name "MANUFACTURER PART NUMBER") "ESP32-WROOM-32E")
        (field (name "LCSC PART #") "C701341")
      )
      (libsource (lib "CommunityVault") (part "CMP-313bfeb3df46eefc-3"))
    )
    (comp (ref "U2")
      (value "TPS63020DSJR")
      (footprint "QFN50P300X400X100_HS-15N")
      (description "High Efficiency Single Inductor Buck-Boost Converter with 4A Switch 14-VSON -40 to 125")
      (fields (field (name "LCSC PART #") "C15483"))
      (libsource (lib "CommunityVault") (part "CMP-70a5b95f396aaf62-2"))
    )
    (comp (ref "U4")
      (value "Analog Devices AD5160BRJZ10-RL7")
      (footprint "TSOP65P280X145-8N")
      (description "Digital Potentiometer 10kOhm 256POS Volatile Linear Automotive 8-Pin SOT-23 T/R")
      (fields
        (field (name "MANUFACTURER PART NUMBER") "AD5160BRJZ10-RL7")
        (field (name "RESISTANCE") "10.0 kΩ")
        (field (name "LCSC PART #") "C40097")
      )
      (libsource (lib "CommunityVault") (part "CMP-6bc4a2c881d8b403-1"))
    )
    (comp (ref "U5")
      (value "REF1933AIDDCT")
      (footprint "SOT95P280X100-5N")
      (description "3.3-V Vref, dual-output Vref & Vref/2 voltage reference 5-SOT-23-THIN -40 to 125")
      (libsource (lib "FavoritesLibrary") (part "SYM-b2327839c6726df5-6"))
    )
    (comp (ref "U6")
      (value "MCP6002T-I/SN")
      (footprint "SOIC127P600X175-8N")
      (description "5MHz 15V/us High Slew-Rate RRIO Operational Amplifier 8-Pin SOIC T/R")
      (fields (field (name "MANUFACTURER PART NUMBER") "TLV9052IDR") (field (name "LCSC PART #") "C7377"))
      (libsource (lib "CommunityVault") (part "CMP-cf0503be886010c2-1"))
    )
    (comp (ref "U7")
      (value "INA126EA/2K5")
      (footprint "TI-DGK8_N")
      (libsource (lib "CommunityVault") (part "CMP-1215678-2"))
    )
    (comp (ref "U9")
      (value "MCP6002T-I/SN")
      (footprint "SOIC127P600X175-8N")
      (description "5MHz 15V/us High Slew-Rate RRIO Operational Amplifier 8-Pin SOIC T/R")
      (fields (field (name "MANUFACTURER PART NUMBER") "TLV9052IDR") (field (name "LCSC PART #") "C7377"))
      (libsource (lib "CommunityVault") (part "CMP-cf0503be886010c2-1"))
    )
    (comp (ref "U10")
      (value "MCP6002T-I/SN")
      (footprint "SOIC127P600X175-8N")
      (description "5MHz 15V/us High Slew-Rate RRIO Operational Amplifier 8-Pin SOIC T/R")
      (fields (field (name "MANUFACTURER PART NUMBER") "TLV9052IDR") (field (name "LCSC PART #") "C7377"))
      (libsource (lib "CommunityVault") (part "CMP-cf0503be886010c2-1"))
    )
  )
  (nets
    (net (code "1") (name "/ADC") (class "Default")
      (node (ref "C13") (pin "1") (pinfunction "1_1") (pintype "passive"))
      (node (ref "R21") (pin "2") (pinfunction "2_2") (pintype "passive"))
      (node (ref "U1") (pin "9") (pinfunction "IO33_9") (pintype "bidirectional"))
      (node (ref "U10") (pin "1") (pinfunction "OUT1_1") (pintype "output"))
    )
    (net (code "2") (name "/BOOT0") (class "Default")
      (node (ref "D7") (pin "1") (pinfunction "1_1") (pintype "passive"))
      (node (ref "U1") (pin "25") (pinfunction "IO0_25") (pintype "bidirectional"))
    )
    (net (code "3") (name "/BUT_A") (class "Default")
      (node (ref "C6") (pin "1") (pinfunction "1_1") (pintype "passive"))
      (node (ref "D1") (pin "2") (pinfunction "2_2") (pintype "passive"))
      (node (ref "R5") (pin "2") (pinfunction "2_2") (pintype "passive"))
      (node (ref "SW1") (pin "2") (pinfunction "2_2") (pintype "passive"))
      (node (ref "U1") (pin "8") (pinfunction "IO32_8") (pintype "bidirectional"))
    )
    (net (code "4") (name "/BUT_B") (class "Default")
      (node (ref "C34") (pin "1") (pinfunction "1_1") (pintype "passive"))
      (node (ref "D2") (pin "2") (pinfunction "2_2") (pintype "passive"))
      (node (ref "R27") (pin "2") (pinfunction "2_2") (pintype "passive"))
      (node (ref "SW2") (pin "2") (pinfunction "2_2") (pintype "passive"))
      (node (ref "U1") (pin "6") (pinfunction "IO34_6") (pintype "bidirectional"))
    )
    (net (code "5") (name "/CABLE_SCREEN") (class "Default")
      (node (ref "U6") (pin "1") (pinfunction "OUT1_1") (pintype "output"))
      (node (ref "U6") (pin "2") (pinfunction "IN1-_2") (pintype "passive"))
    )
    (net (code "6") (name "/CS_N") (class "Default")
      (node (ref "U1") (pin "29") (pinfunction "IO5_29") (pintype "bidirectional"))
      (node (ref "U4") (pin "6") (pinfunction "~{CS}_6") (pintype "input"))
    )
    (net (code "7") (name "/ELECTRODE_N") (class "Default")
      (node (ref "D4") (pin "2") (pinfunction "2_2") (pintype "passive"))
      (node (ref "R13") (pin "2") (pinfunction "2_2") (pintype "passive"))
    )
    (net (code "8") (name "/ELECTRODE_P") (class "Default")
      (node (ref "D5") (pin "2") (pinfunction "2_2") (pintype "passive"))
      (node (ref "R17") (pin "2") (pinfunction "2_2") (pintype "passive"))
    )
    (net (code "9") (name "/ELECTRODE_RLD") (class "Default")
      (node (ref "D3") (pin "2") (pinfunction "2_2") (pintype "passive"))
      (node (ref "R24") (pin "1") (pinfunction "1_1") (pintype "passive"))
    )
    (net (code "10") (name "/ESP32_EN") (class "Default")
      (node (ref "C1") (pin "1") (pinfunction "1_1") (pintype "passive"))
      (node (ref "D8") (pin "1") (pinfunction "1_1") (pintype "passive"))
      (node (ref "R1") (pin "2") (pinfunction "2_2") (pintype "passive"))
      (node (ref "U1") (pin "3") (pinfunction "EN_3") (pintype "input"))
    )
    (net (code "11") (name "/ESP32_RX") (class "Default")
      (node (ref "D10") (pin "1") (pinfunction "1_1") (pintype "passive"))
      (node (ref "U1") (pin "34") (pinfunction "RXD0_34") (pintype "input"))
    )
    (net (code "12") (name "/ESP32_TX") (class "Default")
      (node (ref "D9") (pin "1") (pinfunction "1_1") (pintype "passive"))
      (node (ref "U1") (pin "35") (pinfunction "TXD0_35") (pintype "output"))
    )
    (net (code "13") (name "/FILTER_OUT") (class "Default")
      (node (ref "C14") (pin "2") (pinfunction "2_2") (pintype "passive"))
      (node (ref "C15") (pin "1") (pinfunction "1_1") (pintype "passive"))
      (node (ref "R16") (pin "2") (pinfunction "2_2") (pintype "passive"))
      (node (ref "R20") (pin "1") (pinfunction "1_1") (pintype "passive"))
      (node (ref "U10") (pin "7") (pinfunction "OUT1_7") (pintype "passive"))
    )
    (net (code "14") (name "/GRN_LED") (class "Default")
      (node (ref "R36") (pin "2") (pinfunction "2_2") (pintype "passive"))
      (node (ref "U1") (pin "11") (pinfunction "IO26_11") (pintype "bidirectional"))
    )
    (net (code "15") (name "/INAMP_OUT") (class "Default")
      (node (ref "C27") (pin "1") (pinfunction "1_1") (pintype "passive"))
      (node (ref "C30") (pin "1") (pinfunction "1_1") (pintype "passive"))
      (node (ref "R14") (pin "1") (pinfunction "1_1") (pintype "passive"))
      (node (ref "R18") (pin "2") (pinfunction "2_2") (pintype "passive"))
      (node (ref "R19") (pin "2") (pinfunction "2_2") (pintype "passive"))
      (node (ref "U7") (pin "6") (pinfunction "VO_6") (pintype "output"))
    )
    (net (code "16") (name "/MISO") (class "Default")
      (node (ref "U1") (pin "31") (pinfunction "IO19_31") (pintype "bidirectional"))
    )
    (net (code "17") (name "/MOSI") (class "Default")
      (node (ref "U1") (pin "37") (pinfunction "IO23_37") (pintype "bidirectional"))
      (node (ref "U4") (pin "5") (pinfunction "SDI_5") (pintype "input"))
    )
    (net (code "18") (name "/PA0") (class "Default")
      (node (ref "R23") (pin "1") (pinfunction "1_1") (pintype "passive"))
      (node (ref "R8") (pin "1") (pinfunction "1_1") (pintype "passive"))
      (node (ref "U4") (pin "8") (pinfunction "A_8") (pintype "passive"))
    )
    (net (code "19") (name "/PB0") (class "Default")
      (node (ref "R21") (pin "1") (pinfunction "1_1") (pintype "passive"))
      (node (ref "R26") (pin "1") (pinfunction "1_1") (pintype "passive"))
      (node (ref "U4") (pin "7") (pinfunction "B_7") (pintype "passive"))
    )
    (net (code "20") (name "/PG") (class "Default")
      (node (ref "R38") (pin "1") (pinfunction "1_1") (pintype "passive"))
      (node (ref "U2") (pin "14") (pinfunction "PG_14") (pintype "passive"))
    )
    (net (code "21") (name "/PW0") (class "Default")
      (node (ref "C13") (pin "2") (pinfunction "2_2") (pintype "passive"))
      (node (ref "R23") (pin "2") (pinfunction "2_2") (pintype "passive"))
      (node (ref "R26") (pin "2") (pinfunction "2_2") (pintype "passive"))
      (node (ref "U10") (pin "2") (pinfunction "IN1-_2") (pintype "passive"))
      (node (ref "U4") (pin "1") (pinfunction "W_1") (pintype "passive"))
    )
    (net (code "22") (name "/RED_LED") (class "Default")
      (node (ref "R37") (pin "2") (pinfunction "2_2") (pintype "passive"))
      (node (ref "U1") (pin "16") (pinfunction "IO13_16") (pintype "bidirectional"))
    )
    (net (code "23") (name "/RG1") (class "Default")
      (node (ref "R29") (pin "1") (pinfunction "1_1") (pintype "passive"))
      (node (ref "R7") (pin "1") (pinfunction "1_1") (pintype "passive"))
      (node (ref "U7") (pin "1") (pinfunction "RG_1") (pintype "input"))
    )
    (net (code "24") (name "/RG2") (class "Default")
      (node (ref "R29") (pin "2") (pinfunction "2_2") (pintype "passive"))
      (node (ref "R9") (pin "2") (pinfunction "2_2") (pintype "passive"))
      (node (ref "U7") (pin "8") (pinfunction "RG_8") (pintype "input"))
    )
    (net (code "25") (name "/RLD_BUF") (class "Default")
      (node (ref "R22") (pin "2") (pinfunction "2_2") (pintype "passive"))
      (node (ref "U9") (pin "1") (pinfunction "OUT1_1") (pintype "output"))
      (node (ref "U9") (pin "2") (pinfunction "IN1-_2") (pintype "passive"))
    )
    (net (code "26") (name "/SCK") (class "Default")
      (node (ref "U1") (pin "30") (pinfunction "IO18_30") (pintype "bidirectional"))
      (node (ref "U4") (pin "4") (pinfunction "CLK_4") (pintype "input"))
    )
    (net (code "27") (name "/VBATT_MON") (class "Default")
      (node (ref "C36") (pin "1") (pinfunction "1_1") (pintype "passive"))
      (node (ref "R34") (pin "2") (pinfunction "2_2") (pintype "passive"))
      (node (ref "R35") (pin "1") (pinfunction "1_1") (pintype "passive"))
      (node (ref "U1") (pin "7") (pinfunction "IO35_7") (pintype "bidirectional"))
    )
    (net (code "28") (name "/VFB") (class "Default")
      (node (ref "C4") (pin "2") (pinfunction "2_2") (pintype "passive"))
      (node (ref "R2") (pin "2") (pinfunction "2_2") (pintype "passive"))
      (node (ref "R3") (pin "1") (pinfunction "1_1") (pintype "passive"))
      (node (ref "U2") (pin "3") (pinfunction "FB_3") (pintype "input"))
    )
    (net (code "29") (name "/VREF") (class "Default")
      (node (ref "C18") (pin "1") (pinfunction "1_1") (pintype "passive"))
      (node (ref "C24") (pin "1") (pinfunction "1_1") (pintype "passive"))
      (node (ref "C25") (pin "1") (pinfunction "1_1") (pintype "passive"))
      (node (ref "C26") (pin "1") (pinfunction "1_1") (pintype "passive"))
      (node (ref "C28") (pin "2") (pinfunction "2_2") (pintype "passive"))
      (node (ref "C29") (pin "2") (pinfunction "2_2") (pintype "passive"))
      (node (ref "R10") (pin "1") (pinfunction "1_1") (pintype "passive"))
      (node (ref "R11") (pin "1") (pinfunction "1_1") (pintype "passive"))
      (node (ref "R12") (pin "1") (pinfunction "1_1") (pintype "passive"))
      (node (ref "R25") (pin "1") (pinfunction "1_1") (pintype "passive"))
      (node (ref "R28") (pin "2") (pinfunction "2_2") (pintype "passive"))
      (node (ref "R33") (pin "1") (pinfunction "1_1") (pintype "passive"))
      (node (ref "R8") (pin "2") (pinfunction "2_2") (pintype "passive"))
      (node (ref "U6") (pin "5") (pinfunction "IN2+_5") (pintype "passive"))
      (node (ref "U9") (pin "5") (pinfunction "IN2+_5") (pintype "passive"))
    )
    (net (code "30") (name "3V3") (class "Default")
      (node (ref "C21") (pin "1") (pinfunction "1_1") (pintype "passive"))
      (node (ref "C22") (pin "1") (pinfunction "1_1") (pintype "passive"))
      (node (ref "C4") (pin "1") (pinfunction "1_1") (pintype "passive"))
      (node (ref "C5") (pin "1") (pinfunction "1_1") (pintype "passive"))
      (node (ref "FB1") (pin "1") (pinfunction "1_1") (pintype "passive"))
      (node (ref "R27") (pin "1") (pinfunction "1_1") (pintype "passive"))
      (node (ref "R3") (pin "2") (pinfunction "2_2") (pintype "passive"))
      (node (ref "R38") (pin "2") (pinfunction "2_2") (pintype "passive"))
      (node (ref "R5") (pin "1") (pinfunction "1_1") (pintype "passive"))
      (node (ref "U2") (pin "4") (pinfunction "VOUT_4") (pintype "power_in"))
      (node (ref "U2") (pin "5") (pinfunction "VOUT_5") (pintype "power_in"))
      (node (ref "U5") (pin "3") (pinfunction "EN_3") (pintype "input"))
      (node (ref "U5") (pin "4") (pinfunction "VIN_4") (pintype "power_in"))
    )
    (net (code "31") (name "DBG_PWR") (class "Default")
      (node (ref "SW3") (pin "3") (pinfunction "3_3") (pintype "passive"))
      (node (ref "SW3") (pin "6") (pinfunction "6_6") (pintype "passive"))
    )
    (net (code "32") (name "DVDD") (class "Default")
      (node (ref "C2") (pin "1") (pinfunction "1_1") (pintype "passive"))
      (node (ref "C3") (pin "1") (pinfunction "1_1") (pintype "passive"))
      (node (ref "FB1") (pin "2") (pinfunction "2_2") (pintype "passive"))
      (node (ref "R1") (pin "1") (pinfunction "1_1") (pintype "passive"))
      (node (ref "U1") (pin "2") (pinfunction "3V3_2") (pintype "power_in"))
    )
    (net (code "33") (name "GND") (class "Default")
      (node (ref "C1") (pin "2") (pinfunction "2_2") (pintype "passive"))
      (node (ref "C10") (pin "2") (pinfunction "2_2") (pintype "passive"))
      (node (ref "C11") (pin "2") (pinfunction "2_2") (pintype "passive"))
      (node (ref "C12") (pin "2") (pinfunction "2_2") (pintype "passive"))
      (node (ref "C2") (pin "2") (pinfunction "2_2") (pintype "passive"))
      (node (ref "C21") (pin "2") (pinfunction "2_2") (pintype "passive"))
      (node (ref "C22") (pin "2") (pinfunction "2_2") (pintype "passive"))
      (node (ref "C23") (pin "2") (pinfunction "2_2") (pintype "passive"))
      (node (ref "C24") (pin "2") (pinfunction "2_2") (pintype "passive"))
      (node (ref "C3") (pin "2") (pinfunction "2_2") (pintype "passive"))
      (node (ref "C32") (pin "2") (pinfunction "2_2") (pintype "passive"))
      (node (ref "C33") (pin "2") (pinfunction "2_2") (pintype "passive"))
      (node (ref "C34") (pin "2") (pinfunction "2_2") (pintype "passive"))
      (node (ref "C35") (pin "2") (pinfunction "2_2") (pintype "passive"))
      (node (ref "C36") (pin "2") (pinfunction "2_2") (pintype "passive"))
      (node (ref "C37") (pin "2") (pinfunction "2_2") (pintype "passive"))
      (node (ref "C5") (pin "2") (pinfunction "2_2") (pintype "passive"))
      (node (ref "C6") (pin "2") (pinfunction "2_2") (pintype "passive"))
      (node (ref "C7") (pin "2") (pinfunction "2_2") (pintype "passive"))
      (node (ref "C8") (pin "2") (pinfunction "2_2") (pintype "passive"))
      (node (ref "C9") (pin "2") (pinfunction "2_2") (pintype "passive"))
      (node (ref "D1") (pin "1") (pinfunction "1_1") (pintype "passive"))
      (node (ref "D10") (pin "2") (pinfunction "2_2") (pintype "passive"))
      (node (ref "D11") (pin "2") (pinfunction "K_2") (pintype "passive"))
      (node (ref "D12") (pin "2") (pinfunction "K_2") (pintype "passive"))
      (node (ref "D2") (pin "1") (pinfunction "1_1") (pintype "passive"))
      (node (ref "D3") (pin "1") (pinfunction "1_1") (pintype "passive"))
      (node (ref "D4") (pin "1") (pinfunction "1_1") (pintype "passive"))
      (node (ref "D5") (pin "1") (pinfunction "1_1") (pintype "passive"))
      (node (ref "D6") (pin "1") (pinfunction "1_1") (pintype "passive"))
      (node (ref "D7") (pin "2") (pinfunction "2_2") (pintype "passive"))
      (node (ref "D8") (pin "2") (pinfunction "2_2") (pintype "passive"))
      (node (ref "D9") (pin "2") (pinfunction "2_2") (pintype "passive"))
      (node (ref "P1") (pin "2") (pinfunction "1_2") (pintype "passive"))
      (node (ref "Q1") (pin "1") (pinfunction "G_1") (pintype "passive"))
      (node (ref "R2") (pin "1") (pinfunction "1_1") (pintype "passive"))
      (node (ref "R30") (pin "1") (pinfunction "1_1") (pintype "passive"))
      (node (ref "R35") (pin "2") (pinfunction "2_2") (pintype "passive"))
      (node (ref "R6") (pin "2") (pinfunction "2_2") (pintype "passive"))
      (node (ref "SH1") (pin "1") (pintype "passive"))
      (node (ref "SW1") (pin "1") (pinfunction "1_1") (pintype "passive"))
      (node (ref "SW2") (pin "1") (pinfunction "1_1") (pintype "passive"))
      (node (ref "U1") (pin "1") (pinfunction "GND_1") (pintype "power_in"))
      (node (ref "U1") (pin "15") (pinfunction "GND_15") (pintype "power_in"))
      (node (ref "U1") (pin "38") (pinfunction "GND_38") (pintype "power_in"))
      (node (ref "U1") (pin "39") (pinfunction "EPAD_39") (pintype "power_in"))
      (node (ref "U10") (pin "4") (pinfunction "V-_4") (pintype "power_in"))
      (node (ref "U2") (pin "15") (pinfunction "PGND_15") (pintype "power_in"))
      (node (ref "U2") (pin "2") (pinfunction "GND_2") (pintype "power_in"))
      (node (ref "U4") (pin "3") (pinfunction "GND_3") (pintype "power_in"))
      (node (ref "U5") (pin "2") (pinfunction "GND_2") (pintype "power_in"))
      (node (ref "U6") (pin "4") (pinfunction "V-_4") (pintype "power_in"))
      (node (ref "U7") (pin "4") (pinfunction "V-_4") (pintype "power_in"))
      (node (ref "U9") (pin "4") (pinfunction "V-_4") (pintype "power_in"))
    )
    (net (code "34") (name "Net-(C14-Pad1)") (class "Default")
      (node (ref "C14") (pin "1") (pinfunction "1_1") (pintype "passive"))
      (node (ref "C15") (pin "2") (pinfunction "2_2") (pintype "passive"))
      (node (ref "R10") (pin "2") (pinfunction "2_2") (pintype "passive"))
      (node (ref "R14") (pin "2") (pinfunction "2_2") (pintype "passive"))
      (node (ref "R15") (pin "1") (pinfunction "1_1") (pintype "passive"))
    )
    (net (code "35") (name "Net-(C16-Pad1)") (class "Default")
      (node (ref "C16") (pin "1") (pinfunction "1_1") (pintype "passive"))
      (node (ref "C19") (pin "2") (pinfunction "2_2") (pintype "passive"))
      (node (ref "C28") (pin "1") (pinfunction "1_1") (pintype "passive"))
      (node (ref "R13") (pin "1") (pinfunction "1_1") (pintype "passive"))
    )
    (net (code "36") (name "Net-(C19-Pad1)") (class "Default")
      (node (ref "C19") (pin "1") (pinfunction "1_1") (pintype "passive"))
      (node (ref "C20") (pin "2") (pinfunction "2_2") (pintype "passive"))
      (node (ref "C29") (pin "1") (pinfunction "1_1") (pintype "passive"))
      (node (ref "R17") (pin "1") (pinfunction "1_1") (pintype "passive"))
    )
    (net (code "37") (name "Net-(D11-A)") (class "Default")
      (node (ref "D11") (pin "1") (pinfunction "A_1") (pintype "passive"))
      (node (ref "R36") (pin "1") (pinfunction "1_1") (pintype "passive"))
    )
    (net (code "38") (name "Net-(D12-A)") (class "Default")
      (node (ref "D12") (pin "1") (pinfunction "A_1") (pintype "passive"))
      (node (ref "R37") (pin "1") (pinfunction "1_1") (pintype "passive"))
    )
    (net (code "39") (name "Net-(L1-Pad1)") (class "Default")
      (node (ref "L1") (pin "1") (pinfunction "1_1") (pintype "passive"))
      (node (ref "U2") (pin "8") (pinfunction "L1_8") (pintype "passive"))
      (node (ref "U2") (pin "9") (pinfunction "L1_9") (pintype "passive"))
    )
    (net (code "40") (name "Net-(L1-Pad2)") (class "Default")
      (node (ref "L1") (pin "2") (pinfunction "2_2") (pintype "passive"))
      (node (ref "U2") (pin "6") (pinfunction "L2_6") (pintype "passive"))
      (node (ref "U2") (pin "7") (pinfunction "L2_7") (pintype "passive"))
    )
    (net (code "41") (name "Net-(Q1-D)") (class "Default")
      (node (ref "D6") (pin "2") (pinfunction "2_2") (pintype "passive"))
      (node (ref "Q1") (pin "3") (pinfunction "D_3") (pintype "passive"))
      (node (ref "SW3") (pin "2") (pinfunction "2_2") (pintype "passive"))
      (node (ref "SW3") (pin "5") (pinfunction "5_5") (pintype "passive"))
    )
    (net (code "42") (name "Net-(U2-EN)") (class "Default")
      (node (ref "C8") (pin "1") (pinfunction "1_1") (pintype "passive"))
      (node (ref "R4") (pin "2") (pinfunction "2_2") (pintype "passive"))
      (node (ref "U2") (pin "1") (pinfunction "VINA_1") (pintype "power_in"))
      (node (ref "U2") (pin "12") (pinfunction "EN_12") (pintype "input"))
    )
    (net (code "43") (name "Net-(U2-PS{slash}SYNC)") (class "Default")
      (node (ref "R4") (pin "1") (pinfunction "1_1") (pintype "passive"))
      (node (ref "R6") (pin "1") (pinfunction "1_1") (pintype "passive"))
      (node (ref "U2") (pin "13") (pinfunction "PS/SYNC_13") (pintype "input"))
    )
    (net (code "44") (name "Net-(U5-VBIAS)") (class "Default")
      (node (ref "R33") (pin "2") (pinfunction "2_2") (pintype "passive"))
      (node (ref "U5") (pin "1") (pinfunction "VBIAS_1") (pintype "passive"))
    )
    (net (code "45") (name "Net-(U5-VREF)") (class "Default")
      (node (ref "R32") (pin "2") (pinfunction "2_2") (pintype "passive"))
      (node (ref "U5") (pin "5") (pinfunction "VREF_5") (pintype "power_in"))
    )
    (net (code "46") (name "Net-(U6A-IN1+)") (class "Default")
      (node (ref "C35") (pin "1") (pinfunction "1_1") (pintype "passive"))
      (node (ref "R28") (pin "1") (pinfunction "1_1") (pintype "passive"))
      (node (ref "R30") (pin "2") (pinfunction "2_2") (pintype "passive"))
      (node (ref "U6") (pin "3") (pinfunction "IN1+_3") (pintype "passive"))
    )
    (net (code "47") (name "Net-(U6B-IN2-)") (class "Default")
      (node (ref "C17") (pin "1") (pinfunction "1_1") (pintype "passive"))
      (node (ref "R19") (pin "1") (pinfunction "1_1") (pintype "passive"))
      (node (ref "U6") (pin "6") (pinfunction "IN2-_6") (pintype "passive"))
    )
    (net (code "48") (name "Net-(U6B-OUT1)") (class "Default")
      (node (ref "C17") (pin "2") (pinfunction "2_2") (pintype "passive"))
      (node (ref "U6") (pin "7") (pinfunction "OUT1_7") (pintype "passive"))
      (node (ref "U7") (pin "5") (pinfunction "REF_5") (pintype "input"))
    )
    (net (code "49") (name "Net-(U7-VIN+)") (class "Default")
      (node (ref "C20") (pin "1") (pinfunction "1_1") (pintype "passive"))
      (node (ref "R12") (pin "2") (pinfunction "2_2") (pintype "passive"))
      (node (ref "U7") (pin "3") (pinfunction "VIN+_3") (pintype "input"))
    )
    (net (code "50") (name "Net-(U7-VIN-)") (class "Default")
      (node (ref "C16") (pin "2") (pinfunction "2_2") (pintype "passive"))
      (node (ref "R11") (pin "2") (pinfunction "2_2") (pintype "passive"))
      (node (ref "U7") (pin "2") (pinfunction "VIN-_2") (pintype "input"))
    )
    (net (code "51") (name "Net-(U9A-IN1+)") (class "Default")
      (node (ref "R7") (pin "2") (pinfunction "2_2") (pintype "passive"))
      (node (ref "R9") (pin "1") (pinfunction "1_1") (pintype "passive"))
      (node (ref "U9") (pin "3") (pinfunction "IN1+_3") (pintype "passive"))
    )
    (net (code "52") (name "Net-(U9B-IN2-)") (class "Default")
      (node (ref "C31") (pin "2") (pinfunction "2_2") (pintype "passive"))
      (node (ref "R22") (pin "1") (pinfunction "1_1") (pintype "passive"))
      (node (ref "R31") (pin "1") (pinfunction "1_1") (pintype "passive"))
      (node (ref "U9") (pin "6") (pinfunction "IN2-_6") (pintype "passive"))
    )
    (net (code "53") (name "Net-(U9B-OUT1)") (class "Default")
      (node (ref "C31") (pin "1") (pinfunction "1_1") (pintype "passive"))
      (node (ref "R24") (pin "2") (pinfunction "2_2") (pintype "passive"))
      (node (ref "R31") (pin "2") (pinfunction "2_2") (pintype "passive"))
      (node (ref "U9") (pin "7") (pinfunction "OUT1_7") (pintype "passive"))
    )
    (net (code "54") (name "Net-(U10A-IN1+)") (class "Default")
      (node (ref "C25") (pin "2") (pinfunction "2_2") (pintype "passive"))
      (node (ref "C26") (pin "2") (pinfunction "2_2") (pintype "passive"))
      (node (ref "R16") (pin "1") (pinfunction "1_1") (pintype "passive"))
      (node (ref "U10") (pin "3") (pinfunction "IN1+_3") (pintype "passive"))
    )
    (net (code "55") (name "Net-(U10B-IN2+)") (class "Default")
      (node (ref "C18") (pin "2") (pinfunction "2_2") (pintype "passive"))
      (node (ref "C27") (pin "2") (pinfunction "2_2") (pintype "passive"))
      (node (ref "C30") (pin "2") (pinfunction "2_2") (pintype "passive"))
      (node (ref "R15") (pin "2") (pinfunction "2_2") (pintype "passive"))
      (node (ref "U10") (pin "5") (pinfunction "IN2+_5") (pintype "passive"))
    )
    (net (code "56") (name "Net-(U10B-IN2-)") (class "Default")
      (node (ref "R18") (pin "1") (pinfunction "1_1") (pintype "passive"))
      (node (ref "R20") (pin "2") (pinfunction "2_2") (pintype "passive"))
      (node (ref "R25") (pin "2") (pinfunction "2_2") (pintype "passive"))
      (node (ref "U10") (pin "6") (pinfunction "IN2-_6") (pintype "passive"))
    )
    (net (code "57") (name "VBATT") (class "Default")
      (node (ref "P1") (pin "1") (pinfunction "1_1") (pintype "passive"))
      (node (ref "SW3") (pin "1") (pinfunction "1_1") (pintype "passive"))
      (node (ref "SW3") (pin "4") (pinfunction "4_4") (pintype "passive"))
    )
    (net (code "58") (name "VBATT_SW") (class "Default")
      (node (ref "C32") (pin "1") (pinfunction "1_1") (pintype "passive"))
      (node (ref "C37") (pin "1") (pinfunction "1_1") (pintype "passive"))
      (node (ref "C7") (pin "1") (pinfunction "1_1") (pintype "passive"))
      (node (ref "Q1") (pin "2") (pinfunction "S_2") (pintype "passive"))
      (node (ref "R34") (pin "1") (pinfunction "1_1") (pintype "passive"))
      (node (ref "U2") (pin "10") (pinfunction "VIN_10") (pintype "power_in"))
      (node (ref "U2") (pin "11") (pinfunction "VIN_11") (pintype "power_in"))
    )
    (net (code "59") (name "VCC") (class "Default")
      (node (ref "C10") (pin "1") (pinfunction "1_1") (pintype "passive"))
      (node (ref "C11") (pin "1") (pinfunction "1_1") (pintype "passive"))
      (node (ref "C12") (pin "1") (pinfunction "1_1") (pintype "passive"))
      (node (ref "C23") (pin "1") (pinfunction "1_1") (pintype "passive"))
      (node (ref "C33") (pin "1") (pinfunction "1_1") (pintype "passive"))
      (node (ref "C9") (pin "1") (pinfunction "1_1") (pintype "passive"))
      (node (ref "R32") (pin "1") (pinfunction "1_1") (pintype "passive"))
      (node (ref "U10") (pin "8") (pinfunction "V+_8") (pintype "power_in"))
      (node (ref "U4") (pin "2") (pinfunction "VDD_2") (pintype "power_in"))
      (node (ref "U6") (pin "8") (pinfunction "V+_8") (pintype "power_in"))
      (node (ref "U7") (pin "7") (pinfunction "V+_7") (pintype "power_in"))
      (node (ref "U9") (pin "8") (pinfunction "V+_8") (pintype "power_in"))
    )
    (net (code "60") (name "unconnected-(U1-IO2-Pad24)") (class "Default")
      (node (ref "U1") (pin "24") (pinfunction "IO2_24") (pintype "bidirectional+no_connect"))
    )
    (net (code "61") (name "unconnected-(U1-IO4-Pad26)") (class "Default")
      (node (ref "U1") (pin "26") (pinfunction "IO4_26") (pintype "bidirectional+no_connect"))
    )
    (net (code "62") (name "unconnected-(U1-IO12-Pad14)") (class "Default")
      (node (ref "U1") (pin "14") (pinfunction "IO12_14") (pintype "bidirectional+no_connect"))
    )
    (net (code "63") (name "unconnected-(U1-IO14-Pad13)") (class "Default")
      (node (ref "U1") (pin "13") (pinfunction "IO14_13") (pintype "bidirectional+no_connect"))
    )
    (net (code "64") (name "unconnected-(U1-IO15-Pad23)") (class "Default")
      (node (ref "U1") (pin "23") (pinfunction "IO15_23") (pintype "bidirectional+no_connect"))
    )
    (net (code "65") (name "unconnected-(U1-IO16-Pad27)") (class "Default")
      (node (ref "U1") (pin "27") (pinfunction "IO16_27") (pintype "bidirectional+no_connect"))
    )
    (net (code "66") (name "unconnected-(U1-IO17-Pad28)") (class "Default")
      (node (ref "U1") (pin "28") (pinfunction "IO17_28") (pintype "bidirectional+no_connect"))
    )
    (net (code "67") (name "unconnected-(U1-IO21-Pad33)") (class "Default")
      (node (ref "U1") (pin "33") (pinfunction "IO21_33") (pintype "bidirectional+no_connect"))
    )
    (net (code "68") (name "unconnected-(U1-IO22-Pad36)") (class "Default")
      (node (ref "U1") (pin "36") (pinfunction "IO22_36") (pintype "bidirectional+no_connect"))
    )
    (net (code "69") (name "unconnected-(U1-IO25-Pad10)") (class "Default")
      (node (ref "U1") (pin "10") (pinfunction "IO25_10") (pintype "bidirectional+no_connect"))
    )
    (net (code "70") (name "unconnected-(U1-IO27-Pad12)") (class "Default")
      (node (ref "U1") (pin "12") (pinfunction "IO27_12") (pintype "bidirectional+no_connect"))
    )
    (net (code "71") (name "unconnected-(U1-NC-Pad17)") (class "Default")
      (node (ref "U1") (pin "17") (pinfunction "NC_17") (pintype "passive"))
    )
    (net (code "72") (name "unconnected-(U1-NC-Pad18)") (class "Default")
      (node (ref "U1") (pin "18") (pinfunction "NC_18") (pintype "passive"))
    )
    (net (code "73") (name "unconnected-(U1-NC-Pad19)") (class "Default")
      (node (ref "U1") (pin "19") (pinfunction "NC_19") (pintype "passive"))
    )
    (net (code "74") (name "unconnected-(U1-NC-Pad20)") (class "Default")
      (node (ref "U1") (pin "20") (pinfunction "NC_20") (pintype "passive"))
    )
    (net (code "75") (name "unconnected-(U1-NC-Pad21)") (class "Default")
      (node (ref "U1") (pin "21") (pinfunction "NC_21") (pintype "passive"))
    )
    (net (code "76") (name "unconnected-(U1-NC-Pad22)") (class "Default")
      (node (ref "U1") (pin "22") (pinfunction "NC_22") (pintype "passive"))
    )
    (net (code "77") (name "unconnected-(U1-NC-Pad32)") (class "Default")
      (node (ref "U1") (pin "32") (pinfunction "NC_32") (pintype "passive"))
    )
    (net (code "78") (name "unconnected-(U1-SENSOR_VN-Pad5)") (class "Default")
      (node (ref "U1") (pin "5") (pinfunction "SENSOR_VN_5") (pintype "bidirectional+no_connect"))
    )
    (net (code "79") (name "unconnected-(U1-SENSOR_VP-Pad4)") (class "Default")
      (node (ref "U1") (pin "4") (pinfunction "SENSOR_VP_4") (pintype "bidirectional+no_connect"))
    )
  )
)
